# VREG_AOZ1021AI_5V_3A.net
KiCad netlist of a schematic drawn in Altium Designer
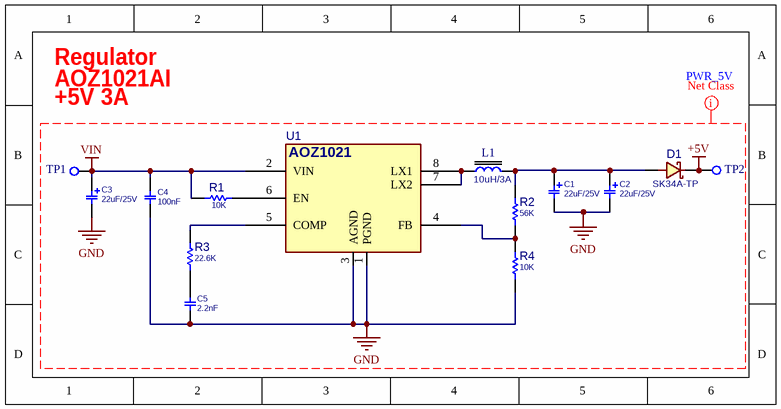
[diagram p0: VREG AOZ1021AI +5V 3A.SchDoc]

(export (version "E")
  (design (tool "Eeschema 10.0.6"))
  (components
    (comp (ref "C1")
      (value "22uF/25V")
      (footprint "C_TN_A")
      (description "CAP, SMD, TAN")
      (libsource (lib "Passive") (part "CAP_SMD_TAN"))
    )
    (comp (ref "C2")
      (value "22uF/25V")
      (footprint "C_TN_A")
      (description "CAP, SMD, TAN")
      (libsource (lib "Passive") (part "CAP_SMD_TAN"))
    )
    (comp (ref "C3")
      (value "22uF/25V")
      (footprint "C_TN_A")
      (description "CAP, SMD, TAN")
      (libsource (lib "Passive") (part "CAP_SMD_TAN"))
    )
    (comp (ref "C4")
      (value "100nF")
      (footprint "C0603S")
      (description "CAP, SMD, MLCC")
      (fields (field (name "MANF_P#") "MANF_PART#") (field (name "MANF") "Murata"))
      (libsource (lib "Passive") (part "CAP_SMD_MLCC"))
    )
    (comp (ref "C5")
      (value "2.2nF")
      (footprint "C0603S")
      (description "CAP, SMD, MLCC")
      (fields (field (name "MANF_P#") "MANF_PART#") (field (name "MANF") "Murata"))
      (libsource (lib "Passive") (part "CAP_SMD_MLCC"))
    )
    (comp (ref "D1")
      (value "SK34A-TP")
      (footprint "D_SMA")
      (description "DIODE, SCHOTTKY, 40V, 3A")
      (fields (field (name "MANF") "Vishay") (field (name "MANF_P#") "SS14-E3"))
      (libsource (lib "PW Components") (part "DIODE_SMD_SCHOTTKY_SK34A-TP"))
    )
    (comp (ref "L1")
      (value "10uH/3A")
      (footprint "L_8X8")
      (description "IND, PWR, SMD")
      (libsource (lib "Passive") (part "INDPWR_SMD"))
    )
    (comp (ref "R1")
      (value "10K")
      (footprint "R0603S")
      (description "RES, SMD")
      (fields (field (name "MANF_P#") "RK73H1ETTP4701F") (field (name "MANF") "KOA SPEER"))
      (libsource (lib "Passive") (part "RES_SMD"))
    )
    (comp (ref "R2")
      (value "56K")
      (footprint "R0603S")
      (description "RES, SMD")
      (fields (field (name "MANF_P#") "RK73H1ETTP4701F") (field (name "MANF") "KOA SPEER"))
      (libsource (lib "Passive") (part "RES_SMD"))
    )
    (comp (ref "R3")
      (value "22.6K")
      (footprint "R0603S")
      (description "RES, SMD")
      (fields (field (name "MANF_P#") "RK73H1ETTP4701F") (field (name "MANF") "KOA SPEER"))
      (libsource (lib "Passive") (part "RES_SMD"))
    )
    (comp (ref "R4")
      (value "10K")
      (footprint "R0603S")
      (description "RES, SMD")
      (fields (field (name "MANF_P#") "RK73H1ETTP4701F") (field (name "MANF") "KOA SPEER"))
      (libsource (lib "Passive") (part "RES_SMD"))
    )
    (comp (ref "TP1")
      (value "Test Point")
      (footprint "TPSMD_C1")
      (libsource (lib "PW Components") (part "Test Point"))
    )
    (comp (ref "TP2")
      (value "Test Point")
      (footprint "TPSMD_C1")
      (libsource (lib "PW Components") (part "Test Point"))
    )
    (comp (ref "U1")
      (value "AOZ1021AI")
      (footprint "SO_8")
      (description "REG, Switching, Buck, 3A, ADJ, 500KHz, 4.5~16VIN, SO-8")
      (fields (field (name "MANF") "AOSMD"))
      (libsource (lib "PW Components") (part "VREG_AOZ1021AI_SO8"))
    )
  )
  (nets
    (net (code "1") (name "+5V") (class "Default")
      (node (ref "D1") (pin "2") (pinfunction "2_2") (pintype "passive"))
      (node (ref "TP2") (pin "1") (pinfunction "TP_1") (pintype "passive"))
    )
    (net (code "2") (name "GND") (class "Default")
      (node (ref "C1") (pin "2") (pinfunction "2_2") (pintype "passive"))
      (node (ref "C2") (pin "2") (pinfunction "2_2") (pintype "passive"))
      (node (ref "C3") (pin "2") (pinfunction "2_2") (pintype "passive"))
      (node (ref "C4") (pin "1") (pinfunction "1_1") (pintype "passive"))
      (node (ref "C5") (pin "1") (pinfunction "1_1") (pintype "passive"))
      (node (ref "R4") (pin "2") (pinfunction "2_2") (pintype "passive"))
      (node (ref "U1") (pin "1") (pinfunction "PGND_1") (pintype "power_in"))
      (node (ref "U1") (pin "3") (pinfunction "AGND_3") (pintype "power_in"))
    )
    (net (code "3") (name "Net-(C1-Pad1)") (class "Default")
      (node (ref "C1") (pin "1") (pinfunction "1_1") (pintype "passive"))
      (node (ref "C2") (pin "1") (pinfunction "1_1") (pintype "passive"))
      (node (ref "D1") (pin "1") (pinfunction "1_1") (pintype "passive"))
      (node (ref "L1") (pin "2") (pinfunction "2_2") (pintype "passive"))
      (node (ref "R2") (pin "1") (pinfunction "1_1") (pintype "passive"))
    )
    (net (code "4") (name "Net-(C5-Pad2)") (class "Default")
      (node (ref "C5") (pin "2") (pinfunction "2_2") (pintype "passive"))
      (node (ref "R3") (pin "2") (pinfunction "2_2") (pintype "passive"))
    )
    (net (code "5") (name "Net-(U1-COMP)") (class "Default")
      (node (ref "R3") (pin "1") (pinfunction "1_1") (pintype "passive"))
      (node (ref "U1") (pin "5") (pinfunction "COMP_5") (pintype "passive"))
    )
    (net (code "6") (name "Net-(U1-EN)") (class "Default")
      (node (ref "R1") (pin "1") (pinfunction "1_1") (pintype "passive"))
      (node (ref "U1") (pin "6") (pinfunction "EN_6") (pintype "passive"))
    )
    (net (code "7") (name "Net-(U1-FB)") (class "Default")
      (node (ref "R2") (pin "2") (pinfunction "2_2") (pintype "passive"))
      (node (ref "R4") (pin "1") (pinfunction "1_1") (pintype "passive"))
      (node (ref "U1") (pin "4") (pinfunction "FB_4") (pintype "passive"))
    )
    (net (code "8") (name "Net-(U1-LX1)") (class "Default")
      (node (ref "L1") (pin "1") (pinfunction "1_1") (pintype "passive"))
      (node (ref "U1") (pin "7") (pinfunction "LX2_7") (pintype "passive"))
      (node (ref "U1") (pin "8") (pinfunction "LX1_8") (pintype "passive"))
    )
    (net (code "9") (name "VIN") (class "Default")
      (node (ref "C3") (pin "1") (pinfunction "1_1") (pintype "passive"))
      (node (ref "C4") (pin "2") (pinfunction "2_2") (pintype "passive"))
      (node (ref "R1") (pin "2") (pinfunction "2_2") (pintype "passive"))
      (node (ref "TP1") (pin "1") (pinfunction "TP_1") (pintype "passive"))
      (node (ref "U1") (pin "2") (pinfunction "VIN_2") (pintype "power_in"))
    )
  )
)
